# source_bt_rev_a.net
KiCad netlist of a schematic drawn in EAGLE
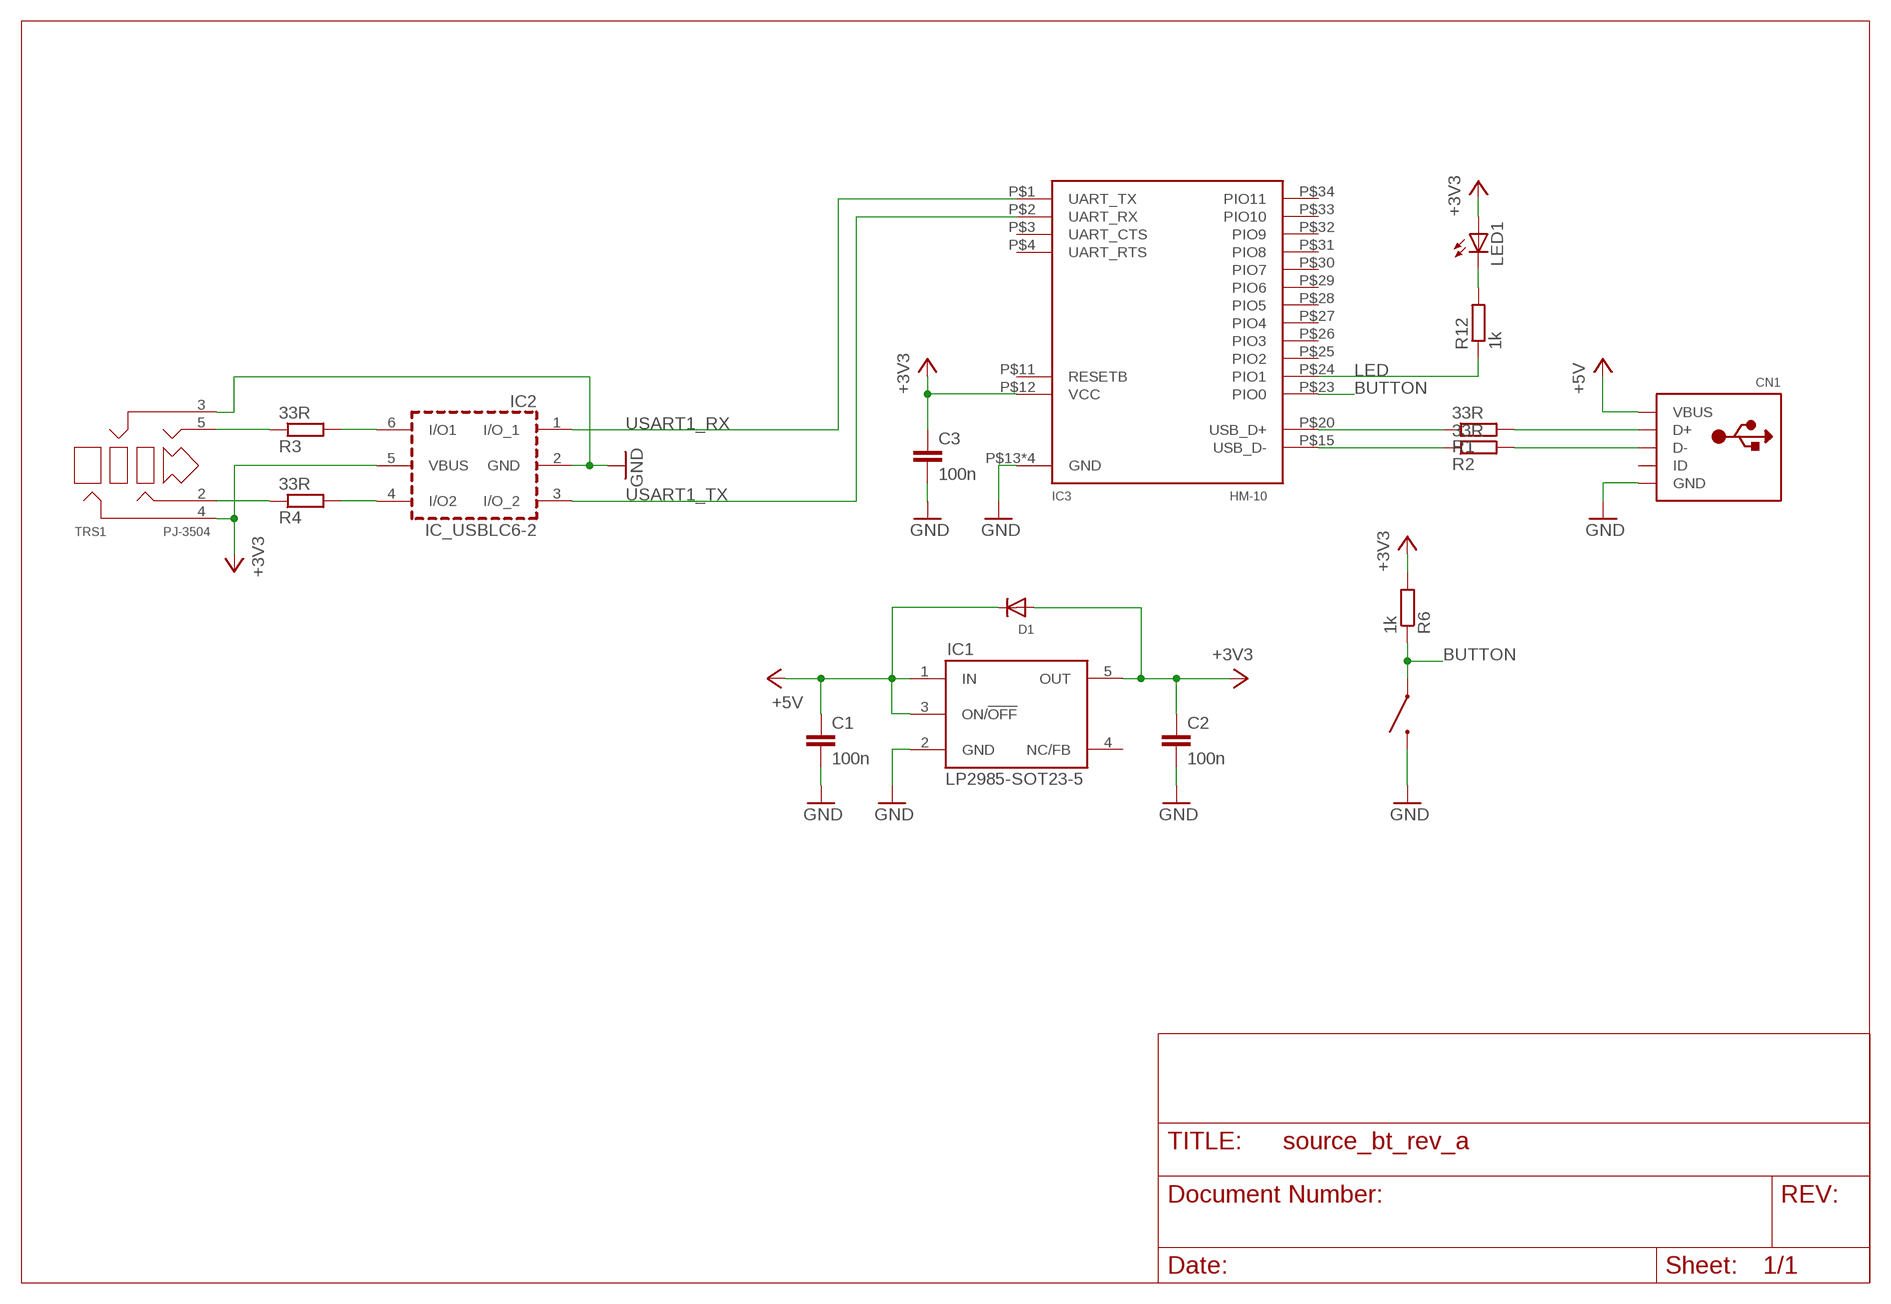
[diagram p0: schematic, sheet 1]

(export (version "E")
  (design (tool "Eeschema 10.0.6"))
  (components
    (comp (ref "C1")
      (value "100n")
      (footprint "eagle-import:C0603")
      (libsource (lib "eagle-import") (part "C-EUC0603"))
    )
    (comp (ref "C2")
      (value "100n")
      (footprint "eagle-import:C0603")
      (libsource (lib "eagle-import") (part "C-EUC0603"))
    )
    (comp (ref "C3")
      (value "100n")
      (footprint "eagle-import:C0603")
      (libsource (lib "eagle-import") (part "C-EUC0603"))
    )
    (comp (ref "CN1")
      (value "USBMINIB")
      (footprint "eagle-import:USB-MINIB")
      (libsource (lib "eagle-import") (part "USBMINIB"))
    )
    (comp (ref "D1")
      (value "DIODESOD-323")
      (footprint "eagle-import:SOD-323")
      (libsource (lib "eagle-import") (part "DIODESOD-323"))
    )
    (comp (ref "IC1")
      (value "LP2985-SOT23-5")
      (footprint "eagle-import:SOT23-5")
      (libsource (lib "eagle-import") (part "LP2985-SOT23-5"))
    )
    (comp (ref "IC2")
      (value "IC_USBLC6-2")
      (footprint "eagle-import:SOT-23-6L")
      (libsource (lib "eagle-import") (part "IC_USBLC6-2"))
    )
    (comp (ref "IC3")
      (value "HM-10")
      (footprint "eagle-import:HM-10")
      (libsource (lib "eagle-import") (part "HM-10"))
    )
    (comp (ref "ISP")
      (value "TACT-SWITCH-40-40")
      (footprint "eagle-import:40-40")
      (libsource (lib "eagle-import") (part "TACT-SWITCH-40-40"))
    )
    (comp (ref "LED1")
      (value "LEDCHIP-LED0603")
      (footprint "eagle-import:CHIP-LED0603")
      (libsource (lib "eagle-import") (part "LEDCHIP-LED0603"))
    )
    (comp (ref "R1")
      (value "33R")
      (footprint "eagle-import:R0603")
      (libsource (lib "eagle-import") (part "R-EU_R0603"))
    )
    (comp (ref "R2")
      (value "33R")
      (footprint "eagle-import:R0603")
      (libsource (lib "eagle-import") (part "R-EU_R0603"))
    )
    (comp (ref "R3")
      (value "33R")
      (footprint "eagle-import:R0603")
      (libsource (lib "eagle-import") (part "R-EU_R0603"))
    )
    (comp (ref "R4")
      (value "33R")
      (footprint "eagle-import:R0603")
      (libsource (lib "eagle-import") (part "R-EU_R0603"))
    )
    (comp (ref "R6")
      (value "1k")
      (footprint "eagle-import:R0603")
      (libsource (lib "eagle-import") (part "R-EU_R0603"))
    )
    (comp (ref "R12")
      (value "1k")
      (footprint "eagle-import:R0603")
      (libsource (lib "eagle-import") (part "R-EU_R0603"))
    )
    (comp (ref "TRS1")
      (value "PJ-3504")
      (footprint "eagle-import:YD-PJ-3504")
      (libsource (lib "eagle-import") (part "PJ-3504"))
    )
  )
  (nets
    (net (code "1") (name "+3V3") (class "Default")
      (node (ref "C2") (pin "1") (pinfunction "1_1") (pintype "passive"))
      (node (ref "C3") (pin "1") (pinfunction "1_1") (pintype "passive"))
      (node (ref "D1") (pin "A") (pinfunction "A_A") (pintype "passive"))
      (node (ref "IC1") (pin "5") (pinfunction "OUT_5") (pintype "bidirectional"))
      (node (ref "IC2") (pin "5") (pinfunction "VBUS_5") (pintype "bidirectional"))
      (node (ref "IC3") (pin "P$12") (pinfunction "VCC_P$12") (pintype "bidirectional"))
      (node (ref "LED1") (pin "A") (pinfunction "A_A") (pintype "passive"))
      (node (ref "R6") (pin "2") (pinfunction "2_2") (pintype "passive"))
      (node (ref "TRS1") (pin "4") (pinfunction "4_4") (pintype "bidirectional"))
    )
    (net (code "2") (name "+5V") (class "Default")
      (node (ref "C1") (pin "1") (pinfunction "1_1") (pintype "passive"))
      (node (ref "CN1") (pin "VBUS") (pinfunction "VBUS_VBUS") (pintype "power_in"))
      (node (ref "D1") (pin "C") (pinfunction "C_C") (pintype "passive"))
      (node (ref "IC1") (pin "1") (pinfunction "IN_1") (pintype "bidirectional"))
      (node (ref "IC1") (pin "3") (pinfunction "ON/~{OFF}_3") (pintype "bidirectional"))
    )
    (net (code "3") (name "/BUTTON") (class "Default")
      (node (ref "IC3") (pin "P$23") (pinfunction "PIO0_P$23") (pintype "bidirectional"))
      (node (ref "ISP") (pin "3") (pinfunction "P$2_3") (pintype "bidirectional"))
      (node (ref "ISP") (pin "4") (pinfunction "P$2_4") (pintype "bidirectional"))
      (node (ref "R6") (pin "1") (pinfunction "1_1") (pintype "passive"))
    )
    (net (code "4") (name "/LED") (class "Default")
      (node (ref "IC3") (pin "P$24") (pinfunction "PIO1_P$24") (pintype "bidirectional"))
      (node (ref "R12") (pin "1") (pinfunction "1_1") (pintype "passive"))
    )
    (net (code "5") (name "/USART1_RX") (class "Default")
      (node (ref "IC2") (pin "1") (pinfunction "I/O_1_1") (pintype "bidirectional"))
      (node (ref "IC3") (pin "P$1") (pinfunction "UART_TX_P$1") (pintype "bidirectional"))
    )
    (net (code "6") (name "/USART1_TX") (class "Default")
      (node (ref "IC2") (pin "3") (pinfunction "I/O_2_3") (pintype "bidirectional"))
      (node (ref "IC3") (pin "P$2") (pinfunction "UART_RX_P$2") (pintype "bidirectional"))
    )
    (net (code "7") (name "GND") (class "Default")
      (node (ref "C1") (pin "2") (pinfunction "2_2") (pintype "passive"))
      (node (ref "C2") (pin "2") (pinfunction "2_2") (pintype "passive"))
      (node (ref "C3") (pin "2") (pinfunction "2_2") (pintype "passive"))
      (node (ref "CN1") (pin "GND") (pinfunction "GND_GND") (pintype "power_in"))
      (node (ref "IC1") (pin "2") (pinfunction "GND_2") (pintype "bidirectional"))
      (node (ref "IC2") (pin "2") (pinfunction "GND_2") (pintype "bidirectional"))
      (node (ref "IC3") (pin "P$13") (pinfunction "GND_P$13") (pintype "bidirectional"))
      (node (ref "IC3") (pin "P$14") (pinfunction "GND_P$14") (pintype "bidirectional"))
      (node (ref "IC3") (pin "P$21") (pinfunction "GND_P$21") (pintype "bidirectional"))
      (node (ref "IC3") (pin "P$22") (pinfunction "GND_P$22") (pintype "bidirectional"))
      (node (ref "ISP") (pin "1") (pinfunction "P$1_1") (pintype "bidirectional"))
      (node (ref "ISP") (pin "2") (pinfunction "P$1_2") (pintype "bidirectional"))
      (node (ref "TRS1") (pin "3") (pinfunction "3_3") (pintype "bidirectional"))
    )
    (net (code "8") (name "Net-(CN1-PadD+)") (class "Default")
      (node (ref "CN1") (pin "D+") (pinfunction "D+_D+") (pintype "bidirectional"))
      (node (ref "R1") (pin "2") (pinfunction "2_2") (pintype "passive"))
    )
    (net (code "9") (name "Net-(CN1-PadD-)") (class "Default")
      (node (ref "CN1") (pin "D-") (pinfunction "D-_D-") (pintype "bidirectional"))
      (node (ref "R2") (pin "2") (pinfunction "2_2") (pintype "passive"))
    )
    (net (code "10") (name "Net-(IC2-I{slash}O1)") (class "Default")
      (node (ref "IC2") (pin "6") (pinfunction "I/O1_6") (pintype "bidirectional"))
      (node (ref "R3") (pin "2") (pinfunction "2_2") (pintype "passive"))
    )
    (net (code "11") (name "Net-(IC2-I{slash}O2)") (class "Default")
      (node (ref "IC2") (pin "4") (pinfunction "I/O2_4") (pintype "bidirectional"))
      (node (ref "R4") (pin "2") (pinfunction "2_2") (pintype "passive"))
    )
    (net (code "12") (name "Net-(IC3-USB_D+)") (class "Default")
      (node (ref "IC3") (pin "P$20") (pinfunction "USB_D+_P$20") (pintype "bidirectional"))
      (node (ref "R1") (pin "1") (pinfunction "1_1") (pintype "passive"))
    )
    (net (code "13") (name "Net-(IC3-USB_D-)") (class "Default")
      (node (ref "IC3") (pin "P$15") (pinfunction "USB_D-_P$15") (pintype "bidirectional"))
      (node (ref "R2") (pin "1") (pinfunction "1_1") (pintype "passive"))
    )
    (net (code "14") (name "Net-(LED1-PadC)") (class "Default")
      (node (ref "LED1") (pin "C") (pinfunction "C_C") (pintype "passive"))
      (node (ref "R12") (pin "2") (pinfunction "2_2") (pintype "passive"))
    )
    (net (code "15") (name "Net-(R3-Pad1)") (class "Default")
      (node (ref "R3") (pin "1") (pinfunction "1_1") (pintype "passive"))
      (node (ref "TRS1") (pin "5") (pinfunction "5_5") (pintype "bidirectional"))
    )
    (net (code "16") (name "Net-(R4-Pad1)") (class "Default")
      (node (ref "R4") (pin "1") (pinfunction "1_1") (pintype "passive"))
      (node (ref "TRS1") (pin "2") (pinfunction "2_2") (pintype "bidirectional"))
    )
    (net (code "17") (name "unconnected-(CN1-PadID)") (class "Default")
      (node (ref "CN1") (pin "ID") (pinfunction "ID_ID") (pintype "bidirectional"))
    )
    (net (code "18") (name "unconnected-(IC1-NC{slash}FB-Pad4)") (class "Default")
      (node (ref "IC1") (pin "4") (pinfunction "NC/FB_4") (pintype "bidirectional"))
    )
    (net (code "19") (name "unconnected-(IC3-PIO2-PadP$25)") (class "Default")
      (node (ref "IC3") (pin "P$25") (pinfunction "PIO2_P$25") (pintype "bidirectional"))
    )
    (net (code "20") (name "unconnected-(IC3-PIO3-PadP$26)") (class "Default")
      (node (ref "IC3") (pin "P$26") (pinfunction "PIO3_P$26") (pintype "bidirectional"))
    )
    (net (code "21") (name "unconnected-(IC3-PIO4-PadP$27)") (class "Default")
      (node (ref "IC3") (pin "P$27") (pinfunction "PIO4_P$27") (pintype "bidirectional"))
    )
    (net (code "22") (name "unconnected-(IC3-PIO5-PadP$28)") (class "Default")
      (node (ref "IC3") (pin "P$28") (pinfunction "PIO5_P$28") (pintype "bidirectional"))
    )
    (net (code "23") (name "unconnected-(IC3-PIO6-PadP$29)") (class "Default")
      (node (ref "IC3") (pin "P$29") (pinfunction "PIO6_P$29") (pintype "bidirectional"))
    )
    (net (code "24") (name "unconnected-(IC3-PIO7-PadP$30)") (class "Default")
      (node (ref "IC3") (pin "P$30") (pinfunction "PIO7_P$30") (pintype "bidirectional"))
    )
    (net (code "25") (name "unconnected-(IC3-PIO8-PadP$31)") (class "Default")
      (node (ref "IC3") (pin "P$31") (pinfunction "PIO8_P$31") (pintype "bidirectional"))
    )
    (net (code "26") (name "unconnected-(IC3-PIO9-PadP$32)") (class "Default")
      (node (ref "IC3") (pin "P$32") (pinfunction "PIO9_P$32") (pintype "bidirectional"))
    )
    (net (code "27") (name "unconnected-(IC3-PIO10-PadP$33)") (class "Default")
      (node (ref "IC3") (pin "P$33") (pinfunction "PIO10_P$33") (pintype "bidirectional"))
    )
    (net (code "28") (name "unconnected-(IC3-PIO11-PadP$34)") (class "Default")
      (node (ref "IC3") (pin "P$34") (pinfunction "PIO11_P$34") (pintype "bidirectional"))
    )
    (net (code "29") (name "unconnected-(IC3-RESETB-PadP$11)") (class "Default")
      (node (ref "IC3") (pin "P$11") (pinfunction "RESETB_P$11") (pintype "bidirectional"))
    )
    (net (code "30") (name "unconnected-(IC3-UART_CTS-PadP$3)") (class "Default")
      (node (ref "IC3") (pin "P$3") (pinfunction "UART_CTS_P$3") (pintype "bidirectional"))
    )
    (net (code "31") (name "unconnected-(IC3-UART_RTS-PadP$4)") (class "Default")
      (node (ref "IC3") (pin "P$4") (pinfunction "UART_RTS_P$4") (pintype "bidirectional"))
    )
  )
)
